# ADC.net
KiCad netlist of a schematic drawn in Altium Designer
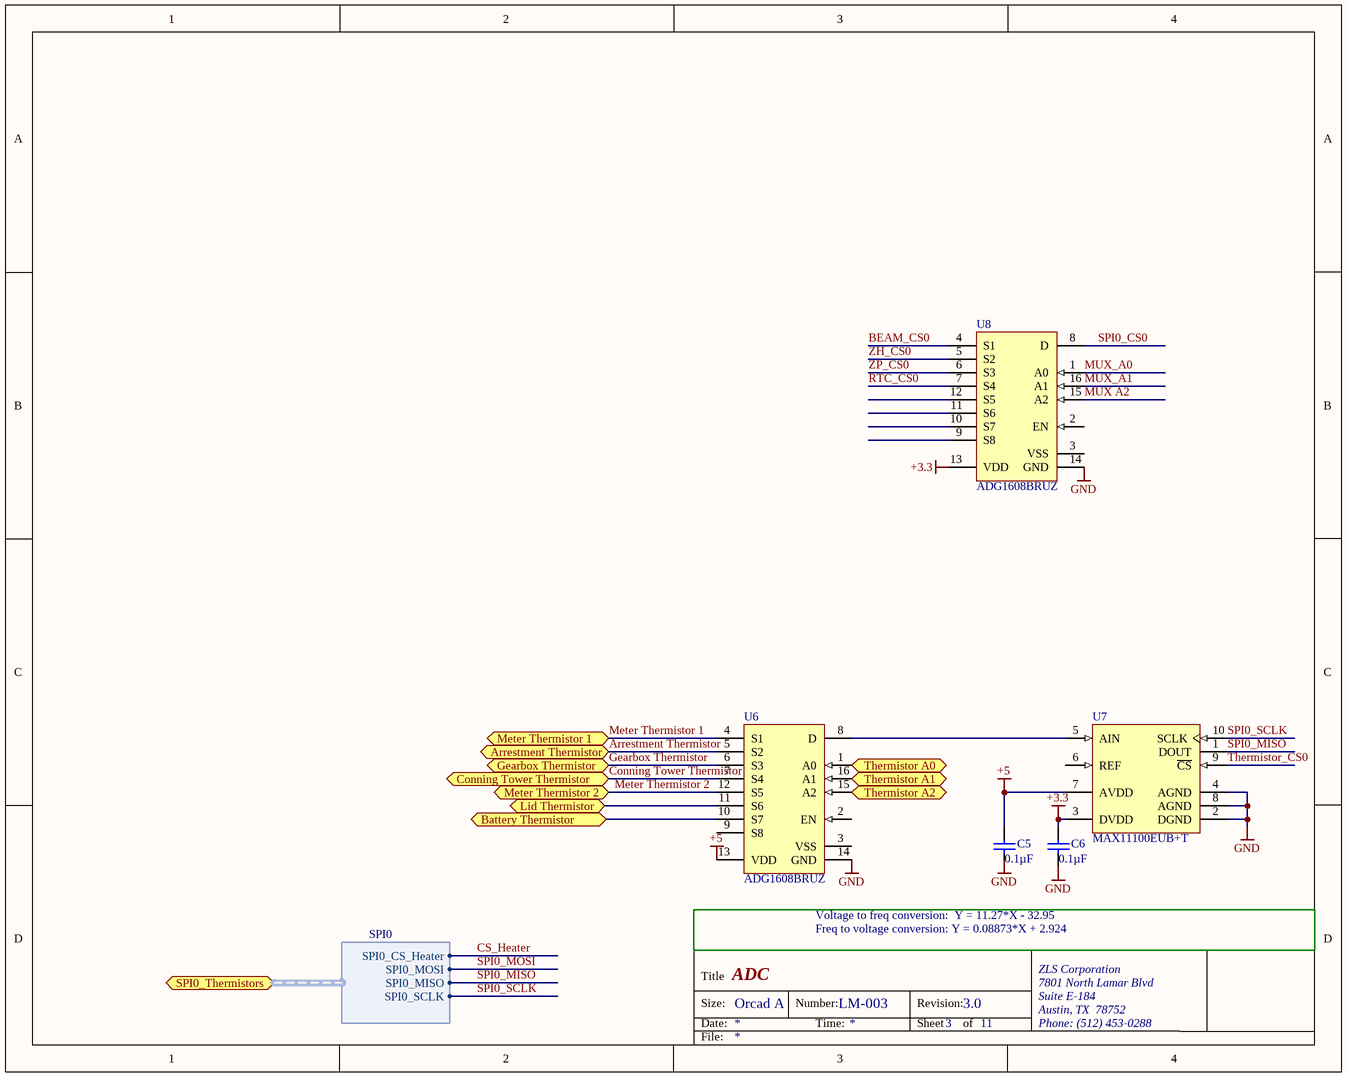
[diagram p0: ADC.SchDoc]

(export (version "E")
  (design (tool "Eeschema 10.0.6"))
  (components
    (comp (ref "C5")
      (value "CAP CER 0.1UF 25V X7R 0805")
      (footprint "CAPC0805(2012)145_N")
      (fields
        (field (name "MANUFACTURER") "Murata Electronics North America")
        (field (name "MANUFACTURER PART NUMBER") "GRM21BR71E104KA01L")
        (field (name "CAPACITANCE") "0.1µF")
        (field (name "TOLERANCE") "±10%")
      )
      (libsource (lib "Altium Content Vault") (part "CMP-1036-04795-1"))
    )
    (comp (ref "C6")
      (value "CAP CER 0.1UF 25V X7R 0805")
      (footprint "CAPC0805(2012)145_N")
      (fields
        (field (name "MANUFACTURER") "Murata Electronics North America")
        (field (name "MANUFACTURER PART NUMBER") "GRM21BR71E104KA01L")
        (field (name "CAPACITANCE") "0.1µF")
        (field (name "TOLERANCE") "±10%")
      )
      (libsource (lib "Altium Content Vault") (part "CMP-1036-04795-1"))
    )
    (comp (ref "U6")
      (value "ADG1608BRUZ")
      (footprint "ADI-RU-16_M")
      (description "4.5 Ohm Ron, 8-Channel +/-5 V,+12 V, +5 V and +3.3 V Multiplexer, 16-pin SOP (RU-16), Tube")
      (fields (field (name "MANUFACTURER") "Analog Devices"))
      (libsource (lib "Altium Content Vault") (part "ADI-ADG1608-RU-16"))
    )
    (comp (ref "U7")
      (value "MAX11100EUB+T")
      (footprint "U10+2_L")
      (description "16-Bit, +5V, 200ksps ADC with 10uA Shutdown, 10-Pin uMAX, -40°C to +85°C, Pb-Free, Tape and Reel")
      (libsource (lib "Altium Content Vault") (part "CON-ADC-MAX11100-IL10"))
    )
    (comp (ref "U8")
      (value "ADG1608BRUZ")
      (footprint "ADI-RU-16_M")
      (description "4.5 Ohm Ron, 8-Channel +/-5 V,+12 V, +5 V and +3.3 V Multiplexer, 16-pin SOP (RU-16), Tube")
      (fields (field (name "MANUFACTURER") "Analog Devices"))
      (libsource (lib "Altium Content Vault") (part "ADI-ADG1608-RU-16"))
    )
  )
  (nets
    (net (code "2") (name "+3.3") (class "Default")
      (node (ref "C6") (pin "1") (pinfunction "1_1") (pintype "passive"))
      (node (ref "U7") (pin "3") (pinfunction "DVDD_3") (pintype "power_in"))
      (node (ref "U8") (pin "13") (pinfunction "VDD_13") (pintype "power_in"))
    )
    (net (code "3") (name "+5") (class "Default")
      (node (ref "C5") (pin "1") (pinfunction "1_1") (pintype "passive"))
      (node (ref "U6") (pin "13") (pinfunction "VDD_13") (pintype "power_in"))
      (node (ref "U7") (pin "7") (pinfunction "AVDD_7") (pintype "power_in"))
    )
    (net (code "4") (name "/Arrestment Thermistor") (class "Default")
      (node (ref "U6") (pin "5") (pinfunction "S2_5") (pintype "passive"))
    )
    (net (code "5") (name "/BEAM_CS0") (class "Default")
      (node (ref "U8") (pin "4") (pinfunction "S1_4") (pintype "passive"))
    )
    (net (code "6") (name "/Battery Thermistor") (class "Default")
      (node (ref "U6") (pin "10") (pinfunction "S7_10") (pintype "passive"))
    )
    (net (code "8") (name "/Conning Tower Thermistor") (class "Default")
      (node (ref "U6") (pin "7") (pinfunction "S4_7") (pintype "passive"))
    )
    (net (code "9") (name "/Gearbox Thermistor") (class "Default")
      (node (ref "U6") (pin "6") (pinfunction "S3_6") (pintype "passive"))
    )
    (net (code "10") (name "/Lid Thermistor") (class "Default")
      (node (ref "U6") (pin "11") (pinfunction "S6_11") (pintype "passive"))
    )
    (net (code "11") (name "/MUX A2") (class "Default")
      (node (ref "U8") (pin "15") (pinfunction "A2_15") (pintype "input"))
    )
    (net (code "12") (name "/MUX_A0") (class "Default")
      (node (ref "U8") (pin "1") (pinfunction "A0_1") (pintype "input"))
    )
    (net (code "13") (name "/MUX_A1") (class "Default")
      (node (ref "U8") (pin "16") (pinfunction "A1_16") (pintype "input"))
    )
    (net (code "14") (name "/Meter Thermistor 1") (class "Default")
      (node (ref "U6") (pin "4") (pinfunction "S1_4") (pintype "passive"))
    )
    (net (code "15") (name "/Meter Thermistor 2") (class "Default")
      (node (ref "U6") (pin "12") (pinfunction "S5_12") (pintype "passive"))
    )
    (net (code "16") (name "/RTC_CS0") (class "Default")
      (node (ref "U8") (pin "7") (pinfunction "S4_7") (pintype "passive"))
    )
    (net (code "17") (name "/SPI0_CS0") (class "Default")
      (node (ref "U8") (pin "8") (pinfunction "D_8") (pintype "passive"))
    )
    (net (code "18") (name "/SPI0_MISO") (class "Default")
      (node (ref "U7") (pin "1") (pinfunction "DOUT_1") (pintype "tri_state"))
    )
    (net (code "20") (name "/SPI0_SCLK") (class "Default")
      (node (ref "U7") (pin "10") (pinfunction "SCLK_10") (pintype "input"))
    )
    (net (code "21") (name "/Thermistor A0") (class "Default")
      (node (ref "U6") (pin "1") (pinfunction "A0_1") (pintype "input"))
    )
    (net (code "22") (name "/Thermistor A1") (class "Default")
      (node (ref "U6") (pin "16") (pinfunction "A1_16") (pintype "input"))
    )
    (net (code "23") (name "/Thermistor A2") (class "Default")
      (node (ref "U6") (pin "15") (pinfunction "A2_15") (pintype "input"))
    )
    (net (code "24") (name "/Thermistor_CS0") (class "Default")
      (node (ref "U7") (pin "9") (pinfunction "~{CS}_9") (pintype "input"))
    )
    (net (code "25") (name "/ZH_CS0") (class "Default")
      (node (ref "U8") (pin "5") (pinfunction "S2_5") (pintype "passive"))
    )
    (net (code "26") (name "/ZP_CS0") (class "Default")
      (node (ref "U8") (pin "6") (pinfunction "S3_6") (pintype "passive"))
    )
    (net (code "28") (name "GND") (class "Default")
      (node (ref "C6") (pin "2") (pinfunction "2_2") (pintype "passive"))
      (node (ref "U6") (pin "14") (pinfunction "GND_14") (pintype "power_in"))
      (node (ref "U7") (pin "2") (pinfunction "DGND_2") (pintype "power_in"))
      (node (ref "U7") (pin "4") (pinfunction "AGND_4") (pintype "power_in"))
      (node (ref "U7") (pin "8") (pinfunction "AGND_8") (pintype "power_in"))
      (node (ref "U8") (pin "14") (pinfunction "GND_14") (pintype "power_in"))
    )
    (net (code "29") (name "Net-(U6-D)") (class "Default")
      (node (ref "U6") (pin "8") (pinfunction "D_8") (pintype "passive"))
      (node (ref "U7") (pin "5") (pinfunction "AIN_5") (pintype "input"))
    )
    (net (code "30") (name "unconnected-(C5-Pad2)") (class "Default")
      (node (ref "C5") (pin "2") (pinfunction "2_2") (pintype "passive"))
    )
    (net (code "31") (name "unconnected-(U6-EN-Pad2)") (class "Default")
      (node (ref "U6") (pin "2") (pinfunction "EN_2") (pintype "input"))
    )
    (net (code "32") (name "unconnected-(U6-S8-Pad9)") (class "Default")
      (node (ref "U6") (pin "9") (pinfunction "S8_9") (pintype "passive"))
    )
    (net (code "33") (name "unconnected-(U6-VSS-Pad3)") (class "Default")
      (node (ref "U6") (pin "3") (pinfunction "VSS_3") (pintype "power_in"))
    )
    (net (code "34") (name "unconnected-(U7-REF-Pad6)") (class "Default")
      (node (ref "U7") (pin "6") (pinfunction "REF_6") (pintype "input"))
    )
    (net (code "35") (name "unconnected-(U8-EN-Pad2)") (class "Default")
      (node (ref "U8") (pin "2") (pinfunction "EN_2") (pintype "input"))
    )
    (net (code "36") (name "unconnected-(U8-S5-Pad12)") (class "Default")
      (node (ref "U8") (pin "12") (pinfunction "S5_12") (pintype "passive"))
    )
    (net (code "37") (name "unconnected-(U8-S6-Pad11)") (class "Default")
      (node (ref "U8") (pin "11") (pinfunction "S6_11") (pintype "passive"))
    )
    (net (code "38") (name "unconnected-(U8-S7-Pad10)") (class "Default")
      (node (ref "U8") (pin "10") (pinfunction "S7_10") (pintype "passive"))
    )
    (net (code "39") (name "unconnected-(U8-S8-Pad9)") (class "Default")
      (node (ref "U8") (pin "9") (pinfunction "S8_9") (pintype "passive"))
    )
    (net (code "40") (name "unconnected-(U8-VSS-Pad3)") (class "Default")
      (node (ref "U8") (pin "3") (pinfunction "VSS_3") (pintype "power_in"))
    )
  )
)
